# drv8353_based_bldc.net
KiCad netlist of a schematic drawn in EAGLE
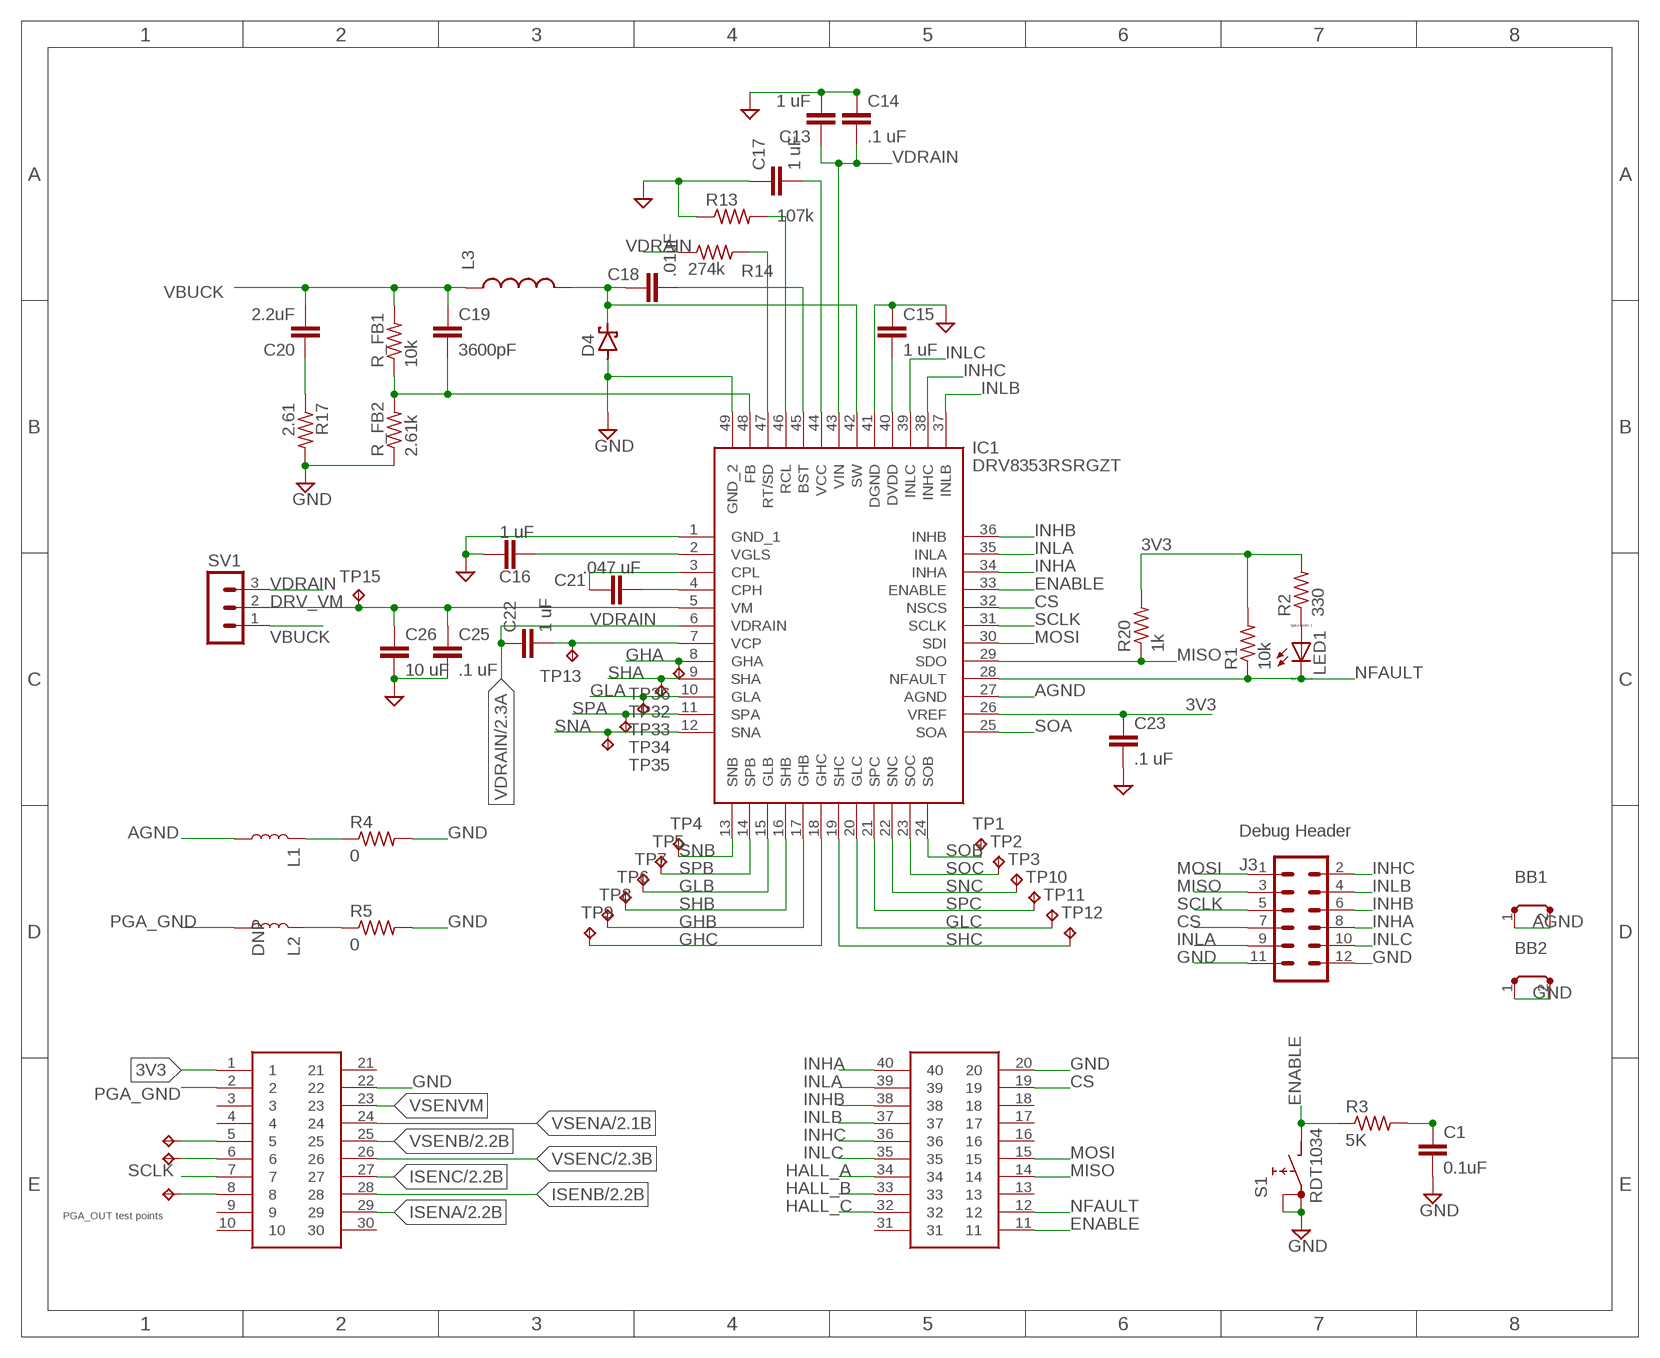
[diagram p0: schematic, sheet 1]
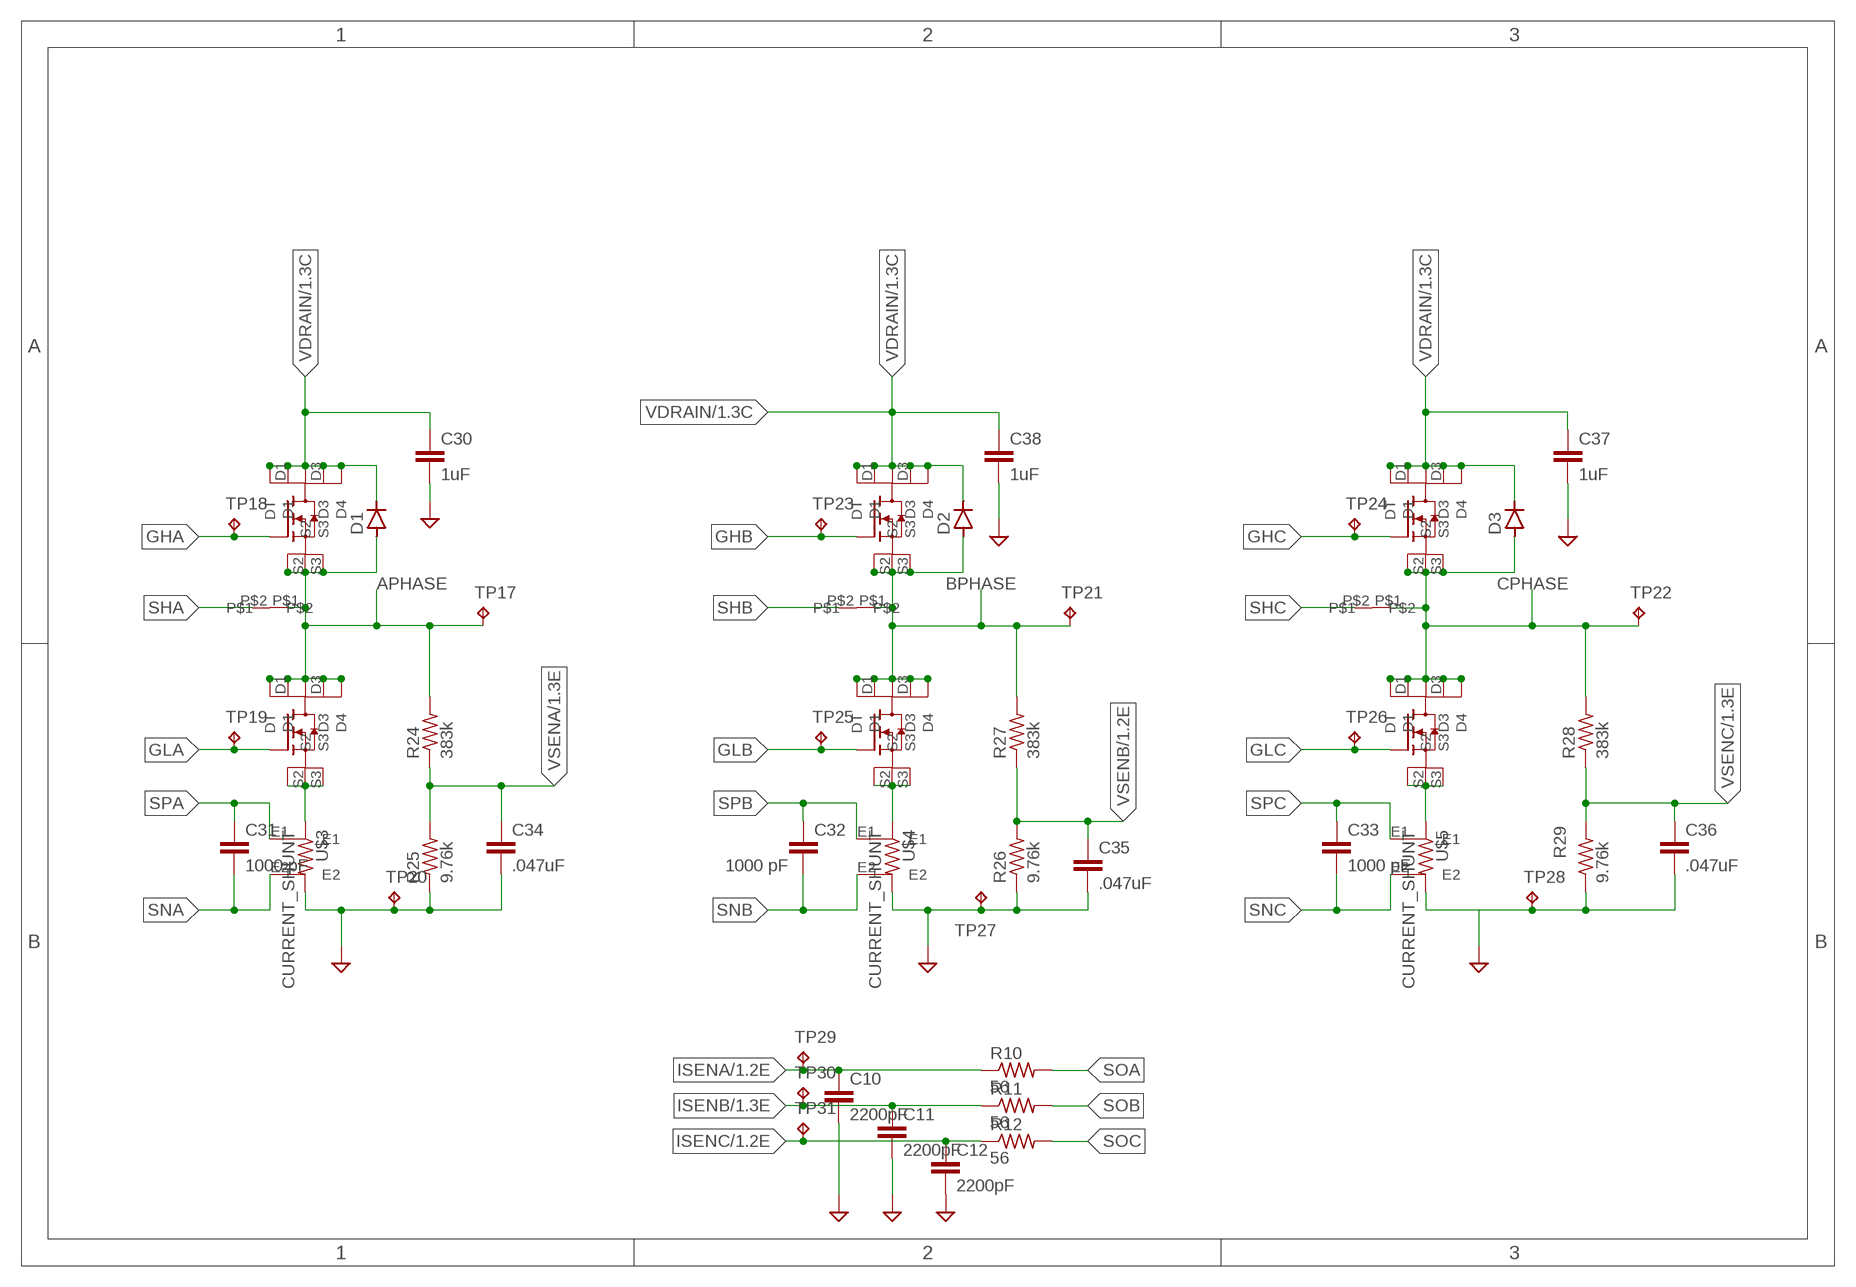
[diagram p1: schematic, sheet 2]
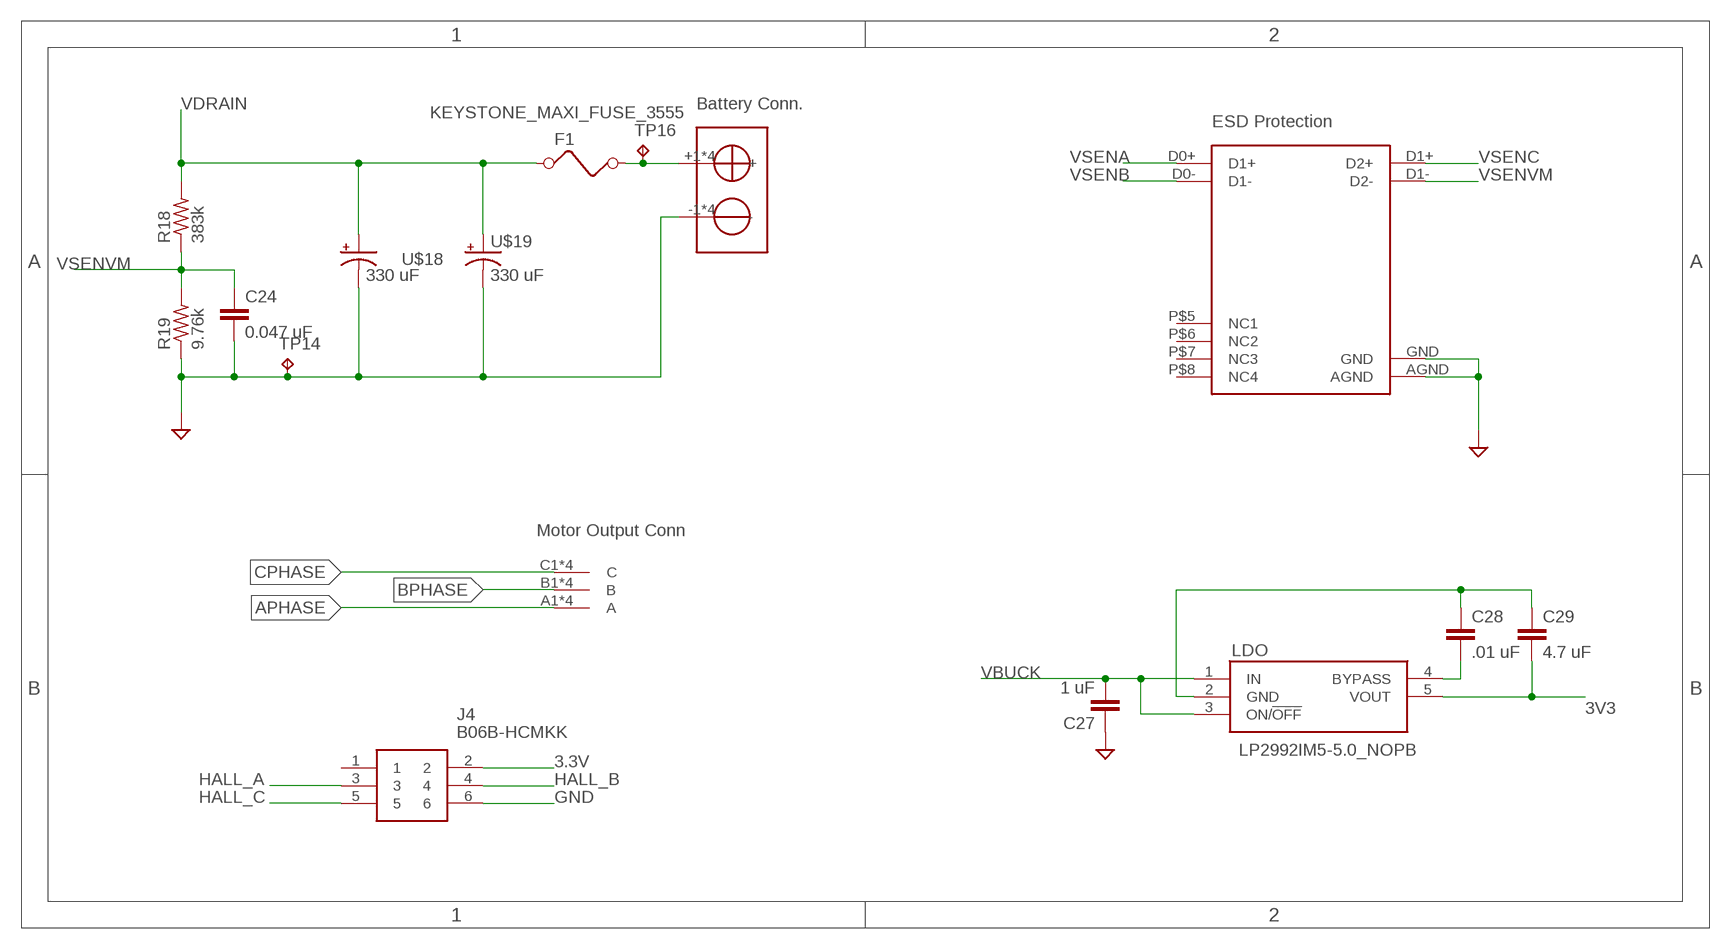
[diagram p2: schematic, sheet 3]

(export (version "E")
  (design (tool "Eeschema 10.0.6"))
  (components
    (comp (ref "BB1")
      (value "TE3/2")
      (footprint "eagle-import:TE3_2")
      (libsource (lib "eagle-import") (part "TE3/2"))
    )
    (comp (ref "BB2")
      (value "TE3/2")
      (footprint "eagle-import:TE3_2")
      (libsource (lib "eagle-import") (part "TE3/2"))
    )
    (comp (ref "C1")
      (value "0.1uF")
      (footprint "eagle-import:C0603K")
      (libsource (lib "eagle-import") (part "resistor_348_C-EUC0603K"))
    )
    (comp (ref "C13")
      (value "1 uF")
      (footprint "eagle-import:C1206K")
      (libsource (lib "eagle-import") (part "C-EUC1206K"))
    )
    (comp (ref "C14")
      (value ".1 uF")
      (footprint "eagle-import:C0805K")
      (libsource (lib "eagle-import") (part "resistor_348_C-EUC0805K"))
    )
    (comp (ref "C15")
      (value "1 uF")
      (footprint "eagle-import:C0603K")
      (libsource (lib "eagle-import") (part "C-EUC0603K"))
    )
    (comp (ref "C16")
      (value "1 uF")
      (footprint "eagle-import:C0603K")
      (libsource (lib "eagle-import") (part "C-EUC0603K"))
    )
    (comp (ref "C17")
      (value "1 uF")
      (footprint "eagle-import:C0603K")
      (libsource (lib "eagle-import") (part "C-EUC0603K"))
    )
    (comp (ref "C18")
      (value ".01uF")
      (footprint "eagle-import:C0603K")
      (libsource (lib "eagle-import") (part "C-EUC0603K"))
    )
    (comp (ref "C19")
      (value "3600pF")
      (footprint "eagle-import:C0603K")
      (libsource (lib "eagle-import") (part "C-EUC0603K"))
    )
    (comp (ref "C20")
      (value "2.2uF")
      (footprint "eagle-import:C0805K")
      (libsource (lib "eagle-import") (part "C-EUC0805K"))
    )
    (comp (ref "C21")
      (value ".047 uF")
      (footprint "eagle-import:C0805K")
      (libsource (lib "eagle-import") (part "C-EUC0805K"))
    )
    (comp (ref "C22")
      (value "1 uF")
      (footprint "eagle-import:C0603K")
      (libsource (lib "eagle-import") (part "resistor_348_C-EUC0603K"))
    )
    (comp (ref "C23")
      (value ".1 uF")
      (footprint "eagle-import:C0603K")
      (libsource (lib "eagle-import") (part "resistor_348_C-EUC0603K"))
    )
    (comp (ref "C25")
      (value ".1 uF")
      (footprint "eagle-import:C0805K")
      (libsource (lib "eagle-import") (part "C-EUC0805K"))
    )
    (comp (ref "C26")
      (value "10 uF")
      (footprint "eagle-import:C2220K")
      (libsource (lib "eagle-import") (part "C-EUC2220K"))
    )
    (comp (ref "D4")
      (value "DFLS1200")
      (footprint "eagle-import:DFLS1200")
      (fields (field (name "SPICEPREFIX") "B"))
      (libsource (lib "eagle-import") (part "DFLS1200"))
    )
    (comp (ref "IC1")
      (value "DRV8353RSRGZT")
      (footprint "eagle-import:QFN50P700X700X100-49N")
      (fields (field (name "MOUSER_PART_NUMBER") "595-DRV8353RSRGZT"))
      (libsource (lib "eagle-import") (part "DRV8353RSRGZT"))
    )
    (comp (ref "J3")
      (value "2X6 FEMALE")
      (footprint "eagle-import:2X6")
      (libsource (lib "eagle-import") (part "CONN_06X2PTH_FEMALE"))
    )
    (comp (ref "L1")
      (value "33nH/±5%/500mA")
      (footprint "eagle-import:0603")
      (libsource (lib "eagle-import") (part "INDUCTOR-0603-33NH"))
    )
    (comp (ref "L2")
      (value "DNP")
      (footprint "eagle-import:0603")
      (libsource (lib "eagle-import") (part "INDUCTOR-0603-33NH"))
    )
    (comp (ref "L3")
      (value "330 uH")
      (footprint "eagle-import:74404084331")
      (libsource (lib "eagle-import") (part "74404084331"))
    )
    (comp (ref "LED1")
      (value "LED_ESML0603")
      (footprint "eagle-import:LED_SML0603")
      (libsource (lib "eagle-import") (part "LED_ESML0603"))
    )
    (comp (ref "R1")
      (value "10k")
      (footprint "eagle-import:R0603")
      (libsource (lib "eagle-import") (part "R-US_R0603"))
    )
    (comp (ref "R2")
      (value "330")
      (footprint "eagle-import:R0603")
      (libsource (lib "eagle-import") (part "R-US_R0603"))
    )
    (comp (ref "R3")
      (value "5K")
      (footprint "eagle-import:R0603")
      (libsource (lib "eagle-import") (part "resistor_348_R-US_R0603"))
    )
    (comp (ref "R4")
      (value "0")
      (footprint "eagle-import:R0603")
      (libsource (lib "eagle-import") (part "resistor_348_R-US_R0603"))
    )
    (comp (ref "R5")
      (value "0")
      (footprint "eagle-import:R0603")
      (libsource (lib "eagle-import") (part "resistor_348_R-US_R0603"))
    )
    (comp (ref "R13")
      (value "107k")
      (footprint "eagle-import:R0603")
      (libsource (lib "eagle-import") (part "R-US_R0603"))
    )
    (comp (ref "R14")
      (value "274k")
      (footprint "eagle-import:R0603")
      (libsource (lib "eagle-import") (part "R-US_R0603"))
    )
    (comp (ref "R17")
      (value "2.61")
      (footprint "eagle-import:R0603")
      (libsource (lib "eagle-import") (part "R-US_R0603"))
    )
    (comp (ref "R20")
      (value "1k")
      (footprint "eagle-import:R0603")
      (libsource (lib "eagle-import") (part "R-US_R0603"))
    )
    (comp (ref "R_FB1")
      (value "10k")
      (footprint "eagle-import:R0603")
      (libsource (lib "eagle-import") (part "R-US_R0603"))
    )
    (comp (ref "R_FB2")
      (value "2.61k")
      (footprint "eagle-import:R0603")
      (libsource (lib "eagle-import") (part "R-US_R0603"))
    )
    (comp (ref "S1")
      (value "RDT1034")
      (footprint "eagle-import:RDT1034")
      (libsource (lib "eagle-import") (part "RDT1034"))
    )
    (comp (ref "SV1")
      (value "MA03-1")
      (footprint "eagle-import:MA03-1")
      (libsource (lib "eagle-import") (part "MA03-1"))
    )
    (comp (ref "TP1")
      (value "TPB1,27")
      (footprint "eagle-import:B1,27")
      (libsource (lib "eagle-import") (part "TPB1,27"))
    )
    (comp (ref "TP2")
      (value "TPB1,27")
      (footprint "eagle-import:B1,27")
      (libsource (lib "eagle-import") (part "TPB1,27"))
    )
    (comp (ref "TP3")
      (value "TPB1,27")
      (footprint "eagle-import:B1,27")
      (libsource (lib "eagle-import") (part "TPB1,27"))
    )
    (comp (ref "TP4")
      (value "TPB1,27")
      (footprint "eagle-import:B1,27")
      (libsource (lib "eagle-import") (part "TPB1,27"))
    )
    (comp (ref "TP5")
      (value "TPB1,27")
      (footprint "eagle-import:B1,27")
      (libsource (lib "eagle-import") (part "TPB1,27"))
    )
    (comp (ref "TP6")
      (value "TPB1,27")
      (footprint "eagle-import:B1,27")
      (libsource (lib "eagle-import") (part "TPB1,27"))
    )
    (comp (ref "TP7")
      (value "TPB1,27")
      (footprint "eagle-import:B1,27")
      (libsource (lib "eagle-import") (part "TPB1,27"))
    )
    (comp (ref "TP8")
      (value "TPB1,27")
      (footprint "eagle-import:B1,27")
      (libsource (lib "eagle-import") (part "TPB1,27"))
    )
    (comp (ref "TP9")
      (value "TPB1,27")
      (footprint "eagle-import:B1,27")
      (libsource (lib "eagle-import") (part "TPB1,27"))
    )
    (comp (ref "TP10")
      (value "TPB1,27")
      (footprint "eagle-import:B1,27")
      (libsource (lib "eagle-import") (part "TPB1,27"))
    )
    (comp (ref "TP11")
      (value "TPB1,27")
      (footprint "eagle-import:B1,27")
      (libsource (lib "eagle-import") (part "TPB1,27"))
    )
    (comp (ref "TP12")
      (value "TPB1,27")
      (footprint "eagle-import:B1,27")
      (libsource (lib "eagle-import") (part "TPB1,27"))
    )
    (comp (ref "TP13")
      (value "TPB1,27")
      (footprint "eagle-import:B1,27")
      (libsource (lib "eagle-import") (part "TPB1,27"))
    )
    (comp (ref "TP15")
      (value "TPB1,27")
      (footprint "eagle-import:B1,27")
      (libsource (lib "eagle-import") (part "TPB1,27"))
    )
    (comp (ref "TP32")
      (value "TPB1,27")
      (footprint "eagle-import:B1,27")
      (libsource (lib "eagle-import") (part "TPB1,27"))
    )
    (comp (ref "TP33")
      (value "TPB1,27")
      (footprint "eagle-import:B1,27")
      (libsource (lib "eagle-import") (part "TPB1,27"))
    )
    (comp (ref "TP34")
      (value "TPB1,27")
      (footprint "eagle-import:B1,27")
      (libsource (lib "eagle-import") (part "TPB1,27"))
    )
    (comp (ref "TP35")
      (value "TPB1,27")
      (footprint "eagle-import:B1,27")
      (libsource (lib "eagle-import") (part "TPB1,27"))
    )
    (comp (ref "TP36")
      (value "TPB1,27")
      (footprint "eagle-import:B1,27")
      (libsource (lib "eagle-import") (part "TPB1,27"))
    )
    (comp (ref "TP37")
      (value "TPB1,27")
      (footprint "eagle-import:B1,27")
      (libsource (lib "eagle-import") (part "TPB1,27"))
    )
    (comp (ref "TP38")
      (value "TPB1,27")
      (footprint "eagle-import:B1,27")
      (libsource (lib "eagle-import") (part "TPB1,27"))
    )
    (comp (ref "TP39")
      (value "TPB1,27")
      (footprint "eagle-import:B1,27")
      (libsource (lib "eagle-import") (part "TPB1,27"))
    )
    (comp (ref "U$2")
      (value "BOOSTER_DOCK")
      (footprint "eagle-import:BOOSTER_DOCK")
      (libsource (lib "eagle-import") (part "BOOSTER_DOCK"))
    )
    (comp (ref "C24")
      (value "0.047 uF")
      (footprint "eagle-import:C0603K")
      (libsource (lib "eagle-import") (part "C-EUC0603K"))
    )
    (comp (ref "C27")
      (value "1 uF")
      (footprint "eagle-import:C0805K")
      (libsource (lib "eagle-import") (part "C-EUC0805K"))
    )
    (comp (ref "C28")
      (value ".01 uF")
      (footprint "eagle-import:C0603K")
      (libsource (lib "eagle-import") (part "C-EUC0603K"))
    )
    (comp (ref "C29")
      (value "4.7 uF")
      (footprint "eagle-import:C1210K")
      (libsource (lib "eagle-import") (part "C-EUC1210K"))
    )
    (comp (ref "F1")
      (value "KEYSTONE_MAXI_FUSE_3555")
      (footprint "eagle-import:KEYSTONE_MAXI_FUSE_CLIP_3555")
      (libsource (lib "eagle-import") (part "KEYSTONE_MAXI_FUSE_3555"))
    )
    (comp (ref "J4")
      (value "B06B-HCMKK")
      (footprint "eagle-import:B06BHCMKK")
      (fields (field (name "MOUSER_PART_NUMBER") "306-B06B-HCMKK"))
      (libsource (lib "eagle-import") (part "B06B-HCMKK"))
    )
    (comp (ref "LDO")
      (value "LP2992IM5-5.0_NOPB")
      (footprint "eagle-import:SOT95P280X145-5N")
      (fields
        (field (name "MANUFACTURER_PART_NUMBER") "LP2992IM5-5.0/NOPB")
        (field (name "MOUSER_PART_NUMBER") "926-2992IM5-5.0/NOPB")
      )
      (libsource (lib "eagle-import") (part "LP2992IM5-5.0_NOPB"))
    )
    (comp (ref "R18")
      (value "383k")
      (footprint "eagle-import:R0603")
      (libsource (lib "eagle-import") (part "R-US_R0603"))
    )
    (comp (ref "R19")
      (value "9.76k")
      (footprint "eagle-import:R0603")
      (libsource (lib "eagle-import") (part "R-US_R0603"))
    )
    (comp (ref "TP14")
      (value "TPB1,27")
      (footprint "eagle-import:B1,27")
      (libsource (lib "eagle-import") (part "TPB1,27"))
    )
    (comp (ref "TP16")
      (value "TPB1,27")
      (footprint "eagle-import:B1,27")
      (libsource (lib "eagle-import") (part "TPB1,27"))
    )
    (comp (ref "TVS_DIODE")
      (value "TPD4S010DQAR")
      (footprint "eagle-import:TPD4S010DQAR")
      (libsource (lib "eagle-import") (part "TPD4S010DQAR"))
    )
    (comp (ref "U$1")
      (value "TRIPPLE-MINI-PP75")
      (footprint "eagle-import:TRIPPLE-MINI-PP75")
      (libsource (lib "eagle-import") (part "TRIPPLE-MINI-PP75"))
    )
    (comp (ref "U$16")
      (value "SB50")
      (footprint "eagle-import:MINI-SB-50")
      (libsource (lib "eagle-import") (part "SB50"))
    )
    (comp (ref "U$18")
      (value "330 uF")
      (footprint "eagle-import:SM_RADIAL_K16_1PRIMARY")
      (libsource (lib "eagle-import") (part "RADIALK16"))
    )
    (comp (ref "U$19")
      (value "330 uF")
      (footprint "eagle-import:SM_RADIAL_K16_1PRIMARY")
      (libsource (lib "eagle-import") (part "RADIALK16"))
    )
    (comp (ref "C10")
      (value "2200pF")
      (footprint "eagle-import:C0603K")
      (libsource (lib "eagle-import") (part "C-EUC0603K"))
    )
    (comp (ref "C11")
      (value "2200pF")
      (footprint "eagle-import:C0603K")
      (libsource (lib "eagle-import") (part "C-EUC0603K"))
    )
    (comp (ref "C12")
      (value "2200pF")
      (footprint "eagle-import:C0603K")
      (libsource (lib "eagle-import") (part "C-EUC0603K"))
    )
    (comp (ref "C30")
      (value "1uF")
      (footprint "eagle-import:C1206")
      (libsource (lib "eagle-import") (part "C-EUC1206"))
    )
    (comp (ref "C31")
      (value "1000 pF")
      (footprint "eagle-import:C0603K")
      (libsource (lib "eagle-import") (part "C-EUC0603K"))
    )
    (comp (ref "C32")
      (value "1000 pF")
      (footprint "eagle-import:C0603K")
      (libsource (lib "eagle-import") (part "C-EUC0603K"))
    )
    (comp (ref "C33")
      (value "1000 pF")
      (footprint "eagle-import:C0603K")
      (libsource (lib "eagle-import") (part "C-EUC0603K"))
    )
    (comp (ref "C34")
      (value ".047uF")
      (footprint "eagle-import:C0603K")
      (libsource (lib "eagle-import") (part "C-EUC0603K"))
    )
    (comp (ref "C35")
      (value ".047uF")
      (footprint "eagle-import:C0603K")
      (libsource (lib "eagle-import") (part "C-EUC0603K"))
    )
    (comp (ref "C36")
      (value ".047uF")
      (footprint "eagle-import:C0603K")
      (libsource (lib "eagle-import") (part "C-EUC0603K"))
    )
    (comp (ref "C37")
      (value "1uF")
      (footprint "eagle-import:C0603K")
      (libsource (lib "eagle-import") (part "C-EUC0603K"))
    )
    (comp (ref "C38")
      (value "1uF")
      (footprint "eagle-import:C0603K")
      (libsource (lib "eagle-import") (part "C-EUC0603K"))
    )
    (comp (ref "D1")
      (value "D-SOD123")
      (footprint "eagle-import:SOD123")
      (libsource (lib "eagle-import") (part "D-SOD123"))
    )
    (comp (ref "D2")
      (value "D-SOD123")
      (footprint "eagle-import:SOD123")
      (libsource (lib "eagle-import") (part "D-SOD123"))
    )
    (comp (ref "D3")
      (value "D-SOD123")
      (footprint "eagle-import:SOD123")
      (libsource (lib "eagle-import") (part "D-SOD123"))
    )
    (comp (ref "R10")
      (value "56")
      (footprint "eagle-import:R0603")
      (libsource (lib "eagle-import") (part "R-US_R0603"))
    )
    (comp (ref "R11")
      (value "56")
      (footprint "eagle-import:R0603")
      (libsource (lib "eagle-import") (part "R-US_R0603"))
    )
    (comp (ref "R12")
      (value "56")
      (footprint "eagle-import:R0603")
      (libsource (lib "eagle-import") (part "R-US_R0603"))
    )
    (comp (ref "R24")
      (value "383k")
      (footprint "eagle-import:R0603")
      (libsource (lib "eagle-import") (part "R-US_R0603"))
    )
    (comp (ref "R25")
      (value "9.76k")
      (footprint "eagle-import:R0603")
      (libsource (lib "eagle-import") (part "R-US_R0603"))
    )
    (comp (ref "R26")
      (value "9.76k")
      (footprint "eagle-import:R0603")
      (libsource (lib "eagle-import") (part "R-US_R0603"))
    )
    (comp (ref "R27")
      (value "383k")
      (footprint "eagle-import:R0603")
      (libsource (lib "eagle-import") (part "R-US_R0603"))
    )
    (comp (ref "R28")
      (value "383k")
      (footprint "eagle-import:R0603")
      (libsource (lib "eagle-import") (part "R-US_R0603"))
    )
    (comp (ref "R29")
      (value "9.76k")
      (footprint "eagle-import:R0603")
      (libsource (lib "eagle-import") (part "R-US_R0603"))
    )
    (comp (ref "TP17")
      (value "TPB1,27")
      (footprint "eagle-import:B1,27")
      (libsource (lib "eagle-import") (part "TPB1,27"))
    )
    (comp (ref "TP18")
      (value "TPB1,27")
      (footprint "eagle-import:B1,27")
      (libsource (lib "eagle-import") (part "TPB1,27"))
    )
    (comp (ref "TP19")
      (value "TPB1,27")
      (footprint "eagle-import:B1,27")
      (libsource (lib "eagle-import") (part "TPB1,27"))
    )
    (comp (ref "TP20")
      (value "TPB1,27")
      (footprint "eagle-import:B1,27")
      (libsource (lib "eagle-import") (part "TPB1,27"))
    )
    (comp (ref "TP21")
      (value "TPB1,27")
      (footprint "eagle-import:B1,27")
      (libsource (lib "eagle-import") (part "TPB1,27"))
    )
    (comp (ref "TP22")
      (value "TPB1,27")
      (footprint "eagle-import:B1,27")
      (libsource (lib "eagle-import") (part "TPB1,27"))
    )
    (comp (ref "TP23")
      (value "TPB1,27")
      (footprint "eagle-import:B1,27")
      (libsource (lib "eagle-import") (part "TPB1,27"))
    )
    (comp (ref "TP24")
      (value "TPB1,27")
      (footprint "eagle-import:B1,27")
      (libsource (lib "eagle-import") (part "TPB1,27"))
    )
    (comp (ref "TP25")
      (value "TPB1,27")
      (footprint "eagle-import:B1,27")
      (libsource (lib "eagle-import") (part "TPB1,27"))
    )
    (comp (ref "TP26")
      (value "TPB1,27")
      (footprint "eagle-import:B1,27")
      (libsource (lib "eagle-import") (part "TPB1,27"))
    )
    (comp (ref "TP27")
      (value "TPB1,27")
      (footprint "eagle-import:B1,27")
      (libsource (lib "eagle-import") (part "TPB1,27"))
    )
    (comp (ref "TP28")
      (value "TPB1,27")
      (footprint "eagle-import:B1,27")
      (libsource (lib "eagle-import") (part "TPB1,27"))
    )
    (comp (ref "TP29")
      (value "TPB1,27")
      (footprint "eagle-import:B1,27")
      (libsource (lib "eagle-import") (part "TPB1,27"))
    )
    (comp (ref "TP30")
      (value "TPB1,27")
      (footprint "eagle-import:B1,27")
      (libsource (lib "eagle-import") (part "TPB1,27"))
    )
    (comp (ref "TP31")
      (value "TPB1,27")
      (footprint "eagle-import:B1,27")
      (libsource (lib "eagle-import") (part "TPB1,27"))
    )
    (comp (ref "U$3")
      (value "CURRENT_SHUNT")
      (footprint "eagle-import:VISH_CSM3637_.002-2")
      (libsource (lib "eagle-import") (part "CURRENT_SHUNT"))
    )
    (comp (ref "U$4")
      (value "CURRENT_SHUNT")
      (footprint "eagle-import:VISH_CSM3637_.002-2")
      (libsource (lib "eagle-import") (part "CURRENT_SHUNT"))
    )
    (comp (ref "U$5")
      (value "CURRENT_SHUNT")
      (footprint "eagle-import:VISH_CSM3637_.002-2")
      (libsource (lib "eagle-import") (part "CURRENT_SHUNT"))
    )
    (comp (ref "U$14")
      (value "NVMTS1D2N08H")
      (footprint "eagle-import:PQFN88")
      (libsource (lib "eagle-import") (part "NVMTS1D2N08H"))
    )
    (comp (ref "U$20")
      (value "NVMTS1D2N08H")
      (footprint "eagle-import:PQFN88")
      (libsource (lib "eagle-import") (part "NVMTS1D2N08H"))
    )
    (comp (ref "U$21")
      (value "NVMTS1D2N08H")
      (footprint "eagle-import:PQFN88")
      (libsource (lib "eagle-import") (part "NVMTS1D2N08H"))
    )
    (comp (ref "U$22")
      (value "NVMTS1D2N08H")
      (footprint "eagle-import:PQFN88")
      (libsource (lib "eagle-import") (part "NVMTS1D2N08H"))
    )
    (comp (ref "U$23")
      (value "NVMTS1D2N08H")
      (footprint "eagle-import:PQFN88")
      (libsource (lib "eagle-import") (part "NVMTS1D2N08H"))
    )
    (comp (ref "U$24")
      (value "NVMTS1D2N08H")
      (footprint "eagle-import:PQFN88")
      (libsource (lib "eagle-import") (part "NVMTS1D2N08H"))
    )
    (comp (ref "U$25")
      (value "NET_TIE")
      (footprint "eagle-import:CNT")
      (libsource (lib "eagle-import") (part "NET_TIE"))
    )
    (comp (ref "U$27")
      (value "NET_TIE")
      (footprint "eagle-import:CNT")
      (libsource (lib "eagle-import") (part "NET_TIE"))
    )
    (comp (ref "U$30")
      (value "NET_TIE")
      (footprint "eagle-import:CNT")
      (libsource (lib "eagle-import") (part "NET_TIE"))
    )
  )
  (nets
    (net (code "1") (name "3.3V") (class "Default")
      (node (ref "J4") (pin "2") (pinfunction "2_2") (pintype "bidirectional"))
    )
    (net (code "2") (name "3V3") (class "Default")
      (node (ref "C23") (pin "1") (pinfunction "1_1") (pintype "passive"))
      (node (ref "C29") (pin "2") (pinfunction "2_2") (pintype "passive"))
      (node (ref "IC1") (pin "26") (pinfunction "VREF_26") (pintype "bidirectional"))
      (node (ref "LDO") (pin "5") (pinfunction "VOUT_5") (pintype "output"))
      (node (ref "R1") (pin "2") (pinfunction "2_2") (pintype "passive"))
      (node (ref "R2") (pin "2") (pinfunction "2_2") (pintype "passive"))
      (node (ref "R20") (pin "2") (pinfunction "2_2") (pintype "passive"))
      (node (ref "U$2") (pin "1") (pinfunction "1_1") (pintype "bidirectional"))
    )
    (net (code "3") (name "AGND") (class "Default")
      (node (ref "BB1") (pin "1") (pinfunction "P_1") (pintype "passive"))
      (node (ref "BB1") (pin "2") (pinfunction "P_2") (pintype "passive"))
      (node (ref "IC1") (pin "27") (pinfunction "AGND_27") (pintype "bidirectional"))
      (node (ref "L1") (pin "1") (pinfunction "1_1") (pintype "passive"))
    )
    (net (code "4") (name "APHASE") (class "Default")
      (node (ref "D1") (pin "2") (pinfunction "A_2") (pintype "passive"))
      (node (ref "R24") (pin "2") (pinfunction "2_2") (pintype "passive"))
      (node (ref "TP17") (pin "TP") (pinfunction "TP_TP") (pintype "input"))
      (node (ref "U$1") (pin "A1") (pinfunction "A_A1") (pintype "bidirectional"))
      (node (ref "U$1") (pin "A2") (pinfunction "A_A2") (pintype "bidirectional"))
      (node (ref "U$1") (pin "A3") (pinfunction "A_A3") (pintype "bidirectional"))
      (node (ref "U$1") (pin "A4") (pinfunction "A_A4") (pintype "bidirectional"))
      (node (ref "U$14") (pin "S1") (pinfunction "S1_S1") (pintype "passive"))
      (node (ref "U$14") (pin "S2") (pinfunction "S2_S2") (pintype "passive"))
      (node (ref "U$14") (pin "S3") (pinfunction "S3_S3") (pintype "passive"))
      (node (ref "U$20") (pin "D1") (pinfunction "D1_D1") (pintype "passive"))
      (node (ref "U$20") (pin "D2") (pinfunction "D2_D2") (pintype "passive"))
      (node (ref "U$20") (pin "D3") (pinfunction "D3_D3") (pintype "passive"))
      (node (ref "U$20") (pin "D4") (pinfunction "D4_D4") (pintype "passive"))
      (node (ref "U$20") (pin "DT") (pinfunction "DT_DT") (pintype "passive"))
      (node (ref "U$25") (pin "P$1") (pinfunction "P$1_P$1") (pintype "bidirectional"))
    )
    (net (code "5") (name "BPHASE") (class "Default")
      (node (ref "D2") (pin "2") (pinfunction "A_2") (pintype "passive"))
      (node (ref "R27") (pin "2") (pinfunction "2_2") (pintype "passive"))
      (node (ref "TP21") (pin "TP") (pinfunction "TP_TP") (pintype "input"))
      (node (ref "U$1") (pin "B1") (pinfunction "B_B1") (pintype "bidirectional"))
      (node (ref "U$1") (pin "B2") (pinfunction "B_B2") (pintype "bidirectional"))
      (node (ref "U$1") (pin "B3") (pinfunction "B_B3") (pintype "bidirectional"))
      (node (ref "U$1") (pin "B4") (pinfunction "B_B4") (pintype "bidirectional"))
      (node (ref "U$21") (pin "D1") (pinfunction "D1_D1") (pintype "passive"))
      (node (ref "U$21") (pin "D2") (pinfunction "D2_D2") (pintype "passive"))
      (node (ref "U$21") (pin "D3") (pinfunction "D3_D3") (pintype "passive"))
      (node (ref "U$21") (pin "D4") (pinfunction "D4_D4") (pintype "passive"))
      (node (ref "U$21") (pin "DT") (pinfunction "DT_DT") (pintype "passive"))
      (node (ref "U$22") (pin "S1") (pinfunction "S1_S1") (pintype "passive"))
      (node (ref "U$22") (pin "S2") (pinfunction "S2_S2") (pintype "passive"))
      (node (ref "U$22") (pin "S3") (pinfunction "S3_S3") (pintype "passive"))
      (node (ref "U$27") (pin "P$1") (pinfunction "P$1_P$1") (pintype "bidirectional"))
    )
    (net (code "6") (name "CPHASE") (class "Default")
      (node (ref "D3") (pin "2") (pinfunction "A_2") (pintype "passive"))
      (node (ref "R28") (pin "2") (pinfunction "2_2") (pintype "passive"))
      (node (ref "TP22") (pin "TP") (pinfunction "TP_TP") (pintype "input"))
      (node (ref "U$1") (pin "C1") (pinfunction "C_C1") (pintype "bidirectional"))
      (node (ref "U$1") (pin "C2") (pinfunction "C_C2") (pintype "bidirectional"))
      (node (ref "U$1") (pin "C3") (pinfunction "C_C3") (pintype "bidirectional"))
      (node (ref "U$1") (pin "C4") (pinfunction "C_C4") (pintype "bidirectional"))
      (node (ref "U$23") (pin "S1") (pinfunction "S1_S1") (pintype "passive"))
      (node (ref "U$23") (pin "S2") (pinfunction "S2_S2") (pintype "passive"))
      (node (ref "U$23") (pin "S3") (pinfunction "S3_S3") (pintype "passive"))
      (node (ref "U$24") (pin "D1") (pinfunction "D1_D1") (pintype "passive"))
      (node (ref "U$24") (pin "D2") (pinfunction "D2_D2") (pintype "passive"))
      (node (ref "U$24") (pin "D3") (pinfunction "D3_D3") (pintype "passive"))
      (node (ref "U$24") (pin "D4") (pinfunction "D4_D4") (pintype "passive"))
      (node (ref "U$24") (pin "DT") (pinfunction "DT_DT") (pintype "passive"))
      (node (ref "U$30") (pin "P$1") (pinfunction "P$1_P$1") (pintype "bidirectional"))
    )
    (net (code "7") (name "CS") (class "Default")
      (node (ref "IC1") (pin "32") (pinfunction "NSCS_32") (pintype "bidirectional"))
      (node (ref "J3") (pin "7") (pinfunction "7_7") (pintype "passive"))
      (node (ref "U$2") (pin "19") (pinfunction "19_19") (pintype "bidirectional"))
    )
    (net (code "8") (name "DRV_VM") (class "Default")
      (node (ref "C25") (pin "1") (pinfunction "1_1") (pintype "passive"))
      (node (ref "C26") (pin "1") (pinfunction "1_1") (pintype "passive"))
      (node (ref "IC1") (pin "5") (pinfunction "VM_5") (pintype "bidirectional"))
      (node (ref "SV1") (pin "2") (pinfunction "2_2") (pintype "passive"))
      (node (ref "TP15") (pin "TP") (pinfunction "TP_TP") (pintype "input"))
    )
    (net (code "9") (name "ENABLE") (class "Default")
      (node (ref "IC1") (pin "33") (pinfunction "ENABLE_33") (pintype "bidirectional"))
      (node (ref "R3") (pin "1") (pinfunction "1_1") (pintype "passive"))
      (node (ref "S1") (pin "B") (pinfunction "B_B") (pintype "passive"))
      (node (ref "U$2") (pin "11") (pinfunction "11_11") (pintype "bidirectional"))
    )
    (net (code "10") (name "GHA") (class "Default")
      (node (ref "IC1") (pin "8") (pinfunction "GHA_8") (pintype "bidirectional"))
      (node (ref "TP18") (pin "TP") (pinfunction "TP_TP") (pintype "input"))
      (node (ref "TP36") (pin "TP") (pinfunction "TP_TP") (pintype "input"))
      (node (ref "U$14") (pin "G") (pinfunction "G_G") (pintype "passive"))
    )
    (net (code "11") (name "GHB") (class "Default")
      (node (ref "IC1") (pin "17") (pinfunction "GHB_17") (pintype "bidirectional"))
      (node (ref "TP23") (pin "TP") (pinfunction "TP_TP") (pintype "input"))
      (node (ref "TP8") (pin "TP") (pinfunction "TP_TP") (pintype "input"))
      (node (ref "U$22") (pin "G") (pinfunction "G_G") (pintype "passive"))
    )
    (net (code "12") (name "GHC") (class "Default")
      (node (ref "IC1") (pin "18") (pinfunction "GHC_18") (pintype "bidirectional"))
      (node (ref "TP24") (pin "TP") (pinfunction "TP_TP") (pintype "input"))
      (node (ref "TP9") (pin "TP") (pinfunction "TP_TP") (pintype "input"))
      (node (ref "U$23") (pin "G") (pinfunction "G_G") (pintype "passive"))
    )
    (net (code "13") (name "GLA") (class "Default")
      (node (ref "IC1") (pin "10") (pinfunction "GLA_10") (pintype "bidirectional"))
      (node (ref "TP19") (pin "TP") (pinfunction "TP_TP") (pintype "input"))
      (node (ref "TP33") (pin "TP") (pinfunction "TP_TP") (pintype "input"))
      (node (ref "U$20") (pin "G") (pinfunction "G_G") (pintype "passive"))
    )
    (net (code "14") (name "GLB") (class "Default")
      (node (ref "IC1") (pin "15") (pinfunction "GLB_15") (pintype "bidirectional"))
      (node (ref "TP25") (pin "TP") (pinfunction "TP_TP") (pintype "input"))
      (node (ref "TP7") (pin "TP") (pinfunction "TP_TP") (pintype "input"))
      (node (ref "U$21") (pin "G") (pinfunction "G_G") (pintype "passive"))
    )
    (net (code "15") (name "GLC") (class "Default")
      (node (ref "IC1") (pin "20") (pinfunction "GLC_20") (pintype "bidirectional"))
      (node (ref "TP11") (pin "TP") (pinfunction "TP_TP") (pintype "input"))
      (node (ref "TP26") (pin "TP") (pinfunction "TP_TP") (pintype "input"))
      (node (ref "U$24") (pin "G") (pinfunction "G_G") (pintype "passive"))
    )
    (net (code "16") (name "GND") (class "Default")
      (node (ref "BB2") (pin "1") (pinfunction "P_1") (pintype "passive"))
      (node (ref "BB2") (pin "2") (pinfunction "P_2") (pintype "passive"))
      (node (ref "C1") (pin "2") (pinfunction "2_2") (pintype "passive"))
      (node (ref "C10") (pin "2") (pinfunction "2_2") (pintype "passive"))
      (node (ref "C11") (pin "2") (pinfunction "2_2") (pintype "passive"))
      (node (ref "C12") (pin "2") (pinfunction "2_2") (pintype "passive"))
      (node (ref "C13") (pin "2") (pinfunction "2_2") (pintype "passive"))
      (node (ref "C14") (pin "1") (pinfunction "1_1") (pintype "passive"))
      (node (ref "C15") (pin "1") (pinfunction "1_1") (pintype "passive"))
      (node (ref "C16") (pin "1") (pinfunction "1_1") (pintype "passive"))
      (node (ref "C17") (pin "1") (pinfunction "1_1") (pintype "passive"))
      (node (ref "C23") (pin "2") (pinfunction "2_2") (pintype "passive"))
      (node (ref "C24") (pin "2") (pinfunction "2_2") (pintype "passive"))
      (node (ref "C25") (pin "2") (pinfunction "2_2") (pintype "passive"))
      (node (ref "C26") (pin "2") (pinfunction "2_2") (pintype "passive"))
      (node (ref "C27") (pin "1") (pinfunction "1_1") (pintype "passive"))
      (node (ref "C30") (pin "2") (pinfunction "2_2") (pintype "passive"))
      (node (ref "C34") (pin "2") (pinfunction "2_2") (pintype "passive"))
      (node (ref "C35") (pin "2") (pinfunction "2_2") (pintype "passive"))
      (node (ref "C36") (pin "2") (pinfunction "2_2") (pintype "passive"))
      (node (ref "C37") (pin "2") (pinfunction "2_2") (pintype "passive"))
      (node (ref "C38") (pin "2") (pinfunction "2_2") (pintype "passive"))
      (node (ref "D4") (pin "GND") (pinfunction "GND_GND") (pintype "passive"))
      (node (ref "IC1") (pin "1") (pinfunction "GND_1_1") (pintype "bidirectional"))
      (node (ref "IC1") (pin "41") (pinfunction "DGND_41") (pintype "bidirectional"))
      (node (ref "IC1") (pin "49") (pinfunction "GND_2_49") (pintype "bidirectional"))
      (node (ref "J3") (pin "11") (pinfunction "11_11") (pintype "passive"))
      (node (ref "J3") (pin "12") (pinfunction "12_12") (pintype "passive"))
      (node (ref "J4") (pin "6") (pinfunction "6_6") (pintype "bidirectional"))
      (node (ref "R13") (pin "1") (pinfunction "1_1") (pintype "passive"))
      (node (ref "R17") (pin "2") (pinfunction "2_2") (pintype "passive"))
      (node (ref "R19") (pin "1") (pinfunction "1_1") (pintype "passive"))
      (node (ref "R25") (pin "1") (pinfunction "1_1") (pintype "passive"))
      (node (ref "R26") (pin "1") (pinfunction "1_1") (pintype "passive"))
      (node (ref "R29") (pin "1") (pinfunction "1_1") (pintype "passive"))
      (node (ref "R4") (pin "2") (pinfunction "2_2") (pintype "passive"))
      (node (ref "R5") (pin "2") (pinfunction "2_2") (pintype "passive"))
      (node (ref "R_FB2") (pin "1") (pinfunction "1_1") (pintype "passive"))
      (node (ref "S1") (pin "A") (pinfunction "A_A") (pintype "passive"))
      (node (ref "S1") (pin "A1") (pinfunction "A1_A1") (pintype "passive"))
      (node (ref "TP14") (pin "TP") (pinfunction "TP_TP") (pintype "input"))
      (node (ref "TP20") (pin "TP") (pinfunction "TP_TP") (pintype "input"))
      (node (ref "TP27") (pin "TP") (pinfunction "TP_TP") (pintype "input"))
      (node (ref "TP28") (pin "TP") (pinfunction "TP_TP") (pintype "input"))
      (node (ref "TVS_DIODE") (pin "AGND") (pinfunction "AGND_AGND") (pintype "bidirectional"))
      (node (ref "TVS_DIODE") (pin "GND") (pinfunction "GND_GND") (pintype "bidirectional"))
      (node (ref "U$16") (pin "-1") (pinfunction "-_-1") (pintype "bidirectional"))
      (node (ref "U$16") (pin "-2") (pinfunction "-_-2") (pintype "bidirectional"))
      (node (ref "U$16") (pin "-3") (pinfunction "-_-3") (pintype "bidirectional"))
      (node (ref "U$16") (pin "-4") (pinfunction "-_-4") (pintype "bidirectional"))
      (node (ref "U$18") (pin "-") (pinfunction "-_-") (pintype "passive"))
      (node (ref "U$19") (pin "-") (pinfunction "-_-") (pintype "passive"))
      (node (ref "U$2") (pin "20") (pinfunction "20_20") (pintype "bidirectional"))
      (node (ref "U$2") (pin "22") (pinfunction "22_22") (pintype "bidirectional"))
      (node (ref "U$3") (pin "I2") (pinfunction "I2_I2") (pintype "passive"))
      (node (ref "U$4") (pin "I2") (pinfunction "I2_I2") (pintype "passive"))
      (node (ref "U$5") (pin "I2") (pinfunction "I2_I2") (pintype "passive"))
    )
    (net (code "17") (name "HALL_A") (class "Default")
      (node (ref "J4") (pin "3") (pinfunction "3_3") (pintype "bidirectional"))
      (node (ref "U$2") (pin "34") (pinfunction "34_34") (pintype "bidirectional"))
    )
    (net (code "18") (name "HALL_B") (class "Default")
      (node (ref "J4") (pin "4") (pinfunction "4_4") (pintype "bidirectional"))
      (node (ref "U$2") (pin "33") (pinfunction "33_33") (pintype "bidirectional"))
    )
    (net (code "19") (name "HALL_C") (class "Default")
      (node (ref "J4") (pin "5") (pinfunction "5_5") (pintype "bidirectional"))
      (node (ref "U$2") (pin "32") (pinfunction "32_32") (pintype "bidirectional"))
    )
    (net (code "20") (name "INHA") (class "Default")
      (node (ref "IC1") (pin "34") (pinfunction "INHA_34") (pintype "bidirectional"))
      (node (ref "J3") (pin "8") (pinfunction "8_8") (pintype "passive"))
      (node (ref "U$2") (pin "40") (pinfunction "40_40") (pintype "bidirectional"))
    )
    (net (code "21") (name "INHB") (class "Default")
      (node (ref "IC1") (pin "36") (pinfunction "INHB_36") (pintype "bidirectional"))
      (node (ref "J3") (pin "6") (pinfunction "6_6") (pintype "passive"))
      (node (ref "U$2") (pin "38") (pinfunction "38_38") (pintype "bidirectional"))
    )
    (net (code "22") (name "INHC") (class "Default")
      (node (ref "IC1") (pin "38") (pinfunction "INHC_38") (pintype "bidirectional"))
      (node (ref "J3") (pin "2") (pinfunction "2_2") (pintype "passive"))
      (node (ref "U$2") (pin "36") (pinfunction "36_36") (pintype "bidirectional"))
    )
    (net (code "23") (name "INLA") (class "Default")
      (node (ref "IC1") (pin "35") (pinfunction "INLA_35") (pintype "bidirectional"))
      (node (ref "J3") (pin "9") (pinfunction "9_9") (pintype "passive"))
      (node (ref "U$2") (pin "39") (pinfunction "39_39") (pintype "bidirectional"))
    )
    (net (code "24") (name "INLB") (class "Default")
      (node (ref "IC1") (pin "37") (pinfunction "INLB_37") (pintype "bidirectional"))
      (node (ref "J3") (pin "4") (pinfunction "4_4") (pintype "passive"))
      (node (ref "U$2") (pin "37") (pinfunction "37_37") (pintype "bidirectional"))
    )
    (net (code "25") (name "INLC") (class "Default")
      (node (ref "IC1") (pin "39") (pinfunction "INLC_39") (pintype "bidirectional"))
      (node (ref "J3") (pin "10") (pinfunction "10_10") (pintype "passive"))
      (node (ref "U$2") (pin "35") (pinfunction "35_35") (pintype "bidirectional"))
    )
    (net (code "26") (name "ISENA") (class "Default")
      (node (ref "C10") (pin "1") (pinfunction "1_1") (pintype "passive"))
      (node (ref "R10") (pin "1") (pinfunction "1_1") (pintype "passive"))
      (node (ref "TP29") (pin "TP") (pinfunction "TP_TP") (pintype "input"))
      (node (ref "U$2") (pin "29") (pinfunction "29_29") (pintype "bidirectional"))
    )
    (net (code "27") (name "ISENB") (class "Default")
      (node (ref "C11") (pin "1") (pinfunction "1_1") (pintype "passive"))
      (node (ref "R11") (pin "1") (pinfunction "1_1") (pintype "passive"))
      (node (ref "TP30") (pin "TP") (pinfunction "TP_TP") (pintype "input"))
      (node (ref "U$2") (pin "28") (pinfunction "28_28") (pintype "bidirectional"))
    )
    (net (code "28") (name "ISENC") (class "Default")
      (node (ref "C12") (pin "1") (pinfunction "1_1") (pintype "passive"))
      (node (ref "R12") (pin "1") (pinfunction "1_1") (pintype "passive"))
      (node (ref "TP31") (pin "TP") (pinfunction "TP_TP") (pintype "input"))
      (node (ref "U$2") (pin "27") (pinfunction "27_27") (pintype "bidirectional"))
    )
    (net (code "29") (name "MISO") (class "Default")
      (node (ref "IC1") (pin "29") (pinfunction "SDO_29") (pintype "bidirectional"))
      (node (ref "J3") (pin "3") (pinfunction "3_3") (pintype "passive"))
      (node (ref "R20") (pin "1") (pinfunction "1_1") (pintype "passive"))
      (node (ref "U$2") (pin "14") (pinfunction "14_14") (pintype "bidirectional"))
    )
    (net (code "30") (name "MOSI") (class "Default")
      (node (ref "IC1") (pin "30") (pinfunction "SDI_30") (pintype "bidirectional"))
      (node (ref "J3") (pin "1") (pinfunction "1_1") (pintype "passive"))
      (node (ref "U$2") (pin "15") (pinfunction "15_15") (pintype "bidirectional"))
    )
    (net (code "31") (name "NFAULT") (class "Default")
      (node (ref "IC1") (pin "28") (pinfunction "NFAULT_28") (pintype "bidirectional"))
      (node (ref "LED1") (pin "C") (pinfunction "C_C") (pintype "passive"))
      (node (ref "R1") (pin "1") (pinfunction "1_1") (pintype "passive"))
      (node (ref "U$2") (pin "12") (pinfunction "12_12") (pintype "bidirectional"))
    )
    (net (code "32") (name "Net-(C1-Pad1)") (class "Default")
      (node (ref "C1") (pin "1") (pinfunction "1_1") (pintype "passive"))
      (node (ref "R3") (pin "2") (pinfunction "2_2") (pintype "passive"))
    )
    (net (code "33") (name "Net-(C20-Pad1)") (class "Default")
      (node (ref "C20") (pin "1") (pinfunction "1_1") (pintype "passive"))
      (node (ref "R17") (pin "1") (pinfunction "1_1") (pintype "passive"))
    )
    (net (code "34") (name "Net-(F1-2-PadB1)") (class "Default")
      (node (ref "F1") (pin "B1") (pinfunction "2_B1") (pintype "passive"))
      (node (ref "F1") (pin "B2") (pinfunction "2_B2") (pintype "passive"))
      (node (ref "TP16") (pin "TP") (pinfunction "TP_TP") (pintype "input"))
      (node (ref "U$16") (pin "+1") (pinfunction "+_+1") (pintype "bidirectional"))
      (node (ref "U$16") (pin "+2") (pinfunction "+_+2") (pintype "bidirectional"))
      (node (ref "U$16") (pin "+3") (pinfunction "+_+3") (pintype "bidirectional"))
      (node (ref "U$16") (pin "+4") (pinfunction "+_+4") (pintype "bidirectional"))
    )
    (net (code "35") (name "Net-(IC1-BST)") (class "Default")
      (node (ref "C18") (pin "2") (pinfunction "2_2") (pintype "passive"))
      (node (ref "IC1") (pin "45") (pinfunction "BST_45") (pintype "bidirectional"))
    )
    (net (code "36") (name "Net-(IC1-CPH)") (class "Default")
      (node (ref "C21") (pin "2") (pinfunction "2_2") (pintype "passive"))
      (node (ref "IC1") (pin "4") (pinfunction "CPH_4") (pintype "bidirectional"))
    )
    (net (code "37") (name "Net-(IC1-CPL)") (class "Default")
      (node (ref "C21") (pin "1") (pinfunction "1_1") (pintype "passive"))
      (node (ref "IC1") (pin "3") (pinfunction "CPL_3") (pintype "bidirectional"))
    )
    (net (code "38") (name "Net-(IC1-DVDD)") (class "Default")
      (node (ref "C15") (pin "2") (pinfunction "2_2") (pintype "passive"))
      (node (ref "IC1") (pin "40") (pinfunction "DVDD_40") (pintype "bidirectional"))
    )
    (net (code "39") (name "Net-(IC1-FB)") (class "Default")
      (node (ref "C19") (pin "2") (pinfunction "2_2") (pintype "passive"))
      (node (ref "IC1") (pin "48") (pinfunction "FB_48") (pintype "bidirectional"))
      (node (ref "R_FB1") (pin "1") (pinfunction "1_1") (pintype "passive"))
      (node (ref "R_FB2") (pin "2") (pinfunction "2_2") (pintype "passive"))
    )
    (net (code "40") (name "Net-(IC1-RCL)") (class "Default")
      (node (ref "IC1") (pin "46") (pinfunction "RCL_46") (pintype "bidirectional"))
      (node (ref "R13") (pin "2") (pinfunction "2_2") (pintype "passive"))
    )
    (net (code "41") (name "Net-(IC1-RT{slash}SD)") (class "Default")
      (node (ref "IC1") (pin "47") (pinfunction "RT/SD_47") (pintype "bidirectional"))
      (node (ref "R14") (pin "2") (pinfunction "2_2") (pintype "passive"))
    )
    (net (code "42") (name "Net-(IC1-SW)") (class "Default")
      (node (ref "C18") (pin "1") (pinfunction "1_1") (pintype "passive"))
      (node (ref "D4") (pin "LINE") (pinfunction "LINE_LINE") (pintype "passive"))
      (node (ref "IC1") (pin "42") (pinfunction "SW_42") (pintype "bidirectional"))
      (node (ref "L3") (pin "P$2") (pinfunction "2_P$2") (pintype "passive"))
    )
    (net (code "43") (name "Net-(IC1-VCC)") (class "Default")
      (node (ref "C17") (pin "2") (pinfunction "2_2") (pintype "passive"))
      (node (ref "IC1") (pin "44") (pinfunction "VCC_44") (pintype "bidirectional"))
    )
    (net (code "44") (name "Net-(IC1-VCP)") (class "Default")
      (node (ref "C22") (pin "2") (pinfunction "2_2") (pintype "passive"))
      (node (ref "IC1") (pin "7") (pinfunction "VCP_7") (pintype "bidirectional"))
      (node (ref "TP13") (pin "TP") (pinfunction "TP_TP") (pintype "input"))
    )
    (net (code "45") (name "Net-(IC1-VGLS)") (class "Default")
      (node (ref "C16") (pin "2") (pinfunction "2_2") (pintype "passive"))
      (node (ref "IC1") (pin "2") (pinfunction "VGLS_2") (pintype "bidirectional"))
    )
    (net (code "46") (name "Net-(L1-Pad2)") (class "Default")
      (node (ref "L1") (pin "2") (pinfunction "2_2") (pintype "passive"))
      (node (ref "R4") (pin "1") (pinfunction "1_1") (pintype "passive"))
    )
    (net (code "47") (name "Net-(L2-Pad2)") (class "Default")
      (node (ref "L2") (pin "2") (pinfunction "2_2") (pintype "passive"))
      (node (ref "R5") (pin "1") (pinfunction "1_1") (pintype "passive"))
    )
    (net (code "48") (name "Net-(LDO-BYPASS)") (class "Default")
      (node (ref "C28") (pin "2") (pinfunction "2_2") (pintype "passive"))
      (node (ref "LDO") (pin "4") (pinfunction "BYPASS_4") (pintype "bidirectional"))
    )
    (net (code "49") (name "Net-(LDO-GND)") (class "Default")
      (node (ref "C28") (pin "1") (pinfunction "1_1") (pintype "passive"))
      (node (ref "C29") (pin "1") (pinfunction "1_1") (pintype "passive"))
      (node (ref "LDO") (pin "2") (pinfunction "GND_2") (pintype "power_in"))
    )
    (net (code "50") (name "Net-(LED1-PadA)") (class "Default")
      (node (ref "LED1") (pin "A") (pinfunction "A_A") (pintype "passive"))
      (node (ref "R2") (pin "1") (pinfunction "1_1") (pintype "passive"))
    )
    (net (code "51") (name "Net-(TP37-PadTP)") (class "Default")
      (node (ref "TP37") (pin "TP") (pinfunction "TP_TP") (pintype "input"))
      (node (ref "U$2") (pin "5") (pinfunction "5_5") (pintype "bidirectional"))
    )
    (net (code "52") (name "Net-(TP38-PadTP)") (class "Default")
      (node (ref "TP38") (pin "TP") (pinfunction "TP_TP") (pintype "input"))
      (node (ref "U$2") (pin "6") (pinfunction "6_6") (pintype "bidirectional"))
    )
    (net (code "53") (name "Net-(TP39-PadTP)") (class "Default")
      (node (ref "TP39") (pin "TP") (pinfunction "TP_TP") (pintype "input"))
      (node (ref "U$2") (pin "8") (pinfunction "8_8") (pintype "bidirectional"))
    )
    (net (code "54") (name "Net-(U$20-PadS1)") (class "Default")
      (node (ref "U$20") (pin "S1") (pinfunction "S1_S1") (pintype "passive"))
      (node (ref "U$20") (pin "S2") (pinfunction "S2_S2") (pintype "passive"))
      (node (ref "U$20") (pin "S3") (pinfunction "S3_S3") (pintype "passive"))
      (node (ref "U$3") (pin "I1") (pinfunction "I1_I1") (pintype "passive"))
    )
    (net (code "55") (name "Net-(U$21-PadS1)") (class "Default")
      (node (ref "U$21") (pin "S1") (pinfunction "S1_S1") (pintype "passive"))
      (node (ref "U$21") (pin "S2") (pinfunction "S2_S2") (pintype "passive"))
      (node (ref "U$21") (pin "S3") (pinfunction "S3_S3") (pintype "passive"))
      (node (ref "U$4") (pin "I1") (pinfunction "I1_I1") (pintype "passive"))
    )
    (net (code "56") (name "Net-(U$24-PadS1)") (class "Default")
      (node (ref "U$24") (pin "S1") (pinfunction "S1_S1") (pintype "passive"))
      (node (ref "U$24") (pin "S2") (pinfunction "S2_S2") (pintype "passive"))
      (node (ref "U$24") (pin "S3") (pinfunction "S3_S3") (pintype "passive"))
      (node (ref "U$5") (pin "I1") (pinfunction "I1_I1") (pintype "passive"))
    )
    (net (code "57") (name "PGA_GND") (class "Default")
      (node (ref "L2") (pin "1") (pinfunction "1_1") (pintype "passive"))
      (node (ref "U$2") (pin "2") (pinfunction "2_2") (pintype "bidirectional"))
    )
    (net (code "58") (name "SCLK") (class "Default")
      (node (ref "IC1") (pin "31") (pinfunction "SCLK_31") (pintype "bidirectional"))
      (node (ref "J3") (pin "5") (pinfunction "5_5") (pintype "passive"))
      (node (ref "U$2") (pin "7") (pinfunction "7_7") (pintype "bidirectional"))
    )
    (net (code "59") (name "SHA") (class "Default")
      (node (ref "IC1") (pin "9") (pinfunction "SHA_9") (pintype "bidirectional"))
      (node (ref "TP32") (pin "TP") (pinfunction "TP_TP") (pintype "input"))
      (node (ref "U$25") (pin "P$2") (pinfunction "P$2_P$2") (pintype "bidirectional"))
    )
    (net (code "60") (name "SHB") (class "Default")
      (node (ref "IC1") (pin "16") (pinfunction "SHB_16") (pintype "bidirectional"))
      (node (ref "TP6") (pin "TP") (pinfunction "TP_TP") (pintype "input"))
      (node (ref "U$27") (pin "P$2") (pinfunction "P$2_P$2") (pintype "bidirectional"))
    )
    (net (code "61") (name "SHC") (class "Default")
      (node (ref "IC1") (pin "19") (pinfunction "SHC_19") (pintype "bidirectional"))
      (node (ref "TP12") (pin "TP") (pinfunction "TP_TP") (pintype "input"))
      (node (ref "U$30") (pin "P$2") (pinfunction "P$2_P$2") (pintype "bidirectional"))
    )
    (net (code "62") (name "SNA") (class "Default")
      (node (ref "C31") (pin "2") (pinfunction "2_2") (pintype "passive"))
      (node (ref "IC1") (pin "12") (pinfunction "SNA_12") (pintype "bidirectional"))
      (node (ref "TP35") (pin "TP") (pinfunction "TP_TP") (pintype "input"))
      (node (ref "U$3") (pin "E2") (pinfunction "E2_E2") (pintype "bidirectional"))
    )
    (net (code "63") (name "SNB") (class "Default")
      (node (ref "C32") (pin "2") (pinfunction "2_2") (pintype "passive"))
      (node (ref "IC1") (pin "13") (pinfunction "SNB_13") (pintype "bidirectional"))
      (node (ref "TP4") (pin "TP") (pinfunction "TP_TP") (pintype "input"))
      (node (ref "U$4") (pin "E2") (pinfunction "E2_E2") (pintype "bidirectional"))
    )
    (net (code "64") (name "SNC") (class "Default")
      (node (ref "C33") (pin "2") (pinfunction "2_2") (pintype "passive"))
      (node (ref "IC1") (pin "22") (pinfunction "SNC_22") (pintype "bidirectional"))
      (node (ref "TP3") (pin "TP") (pinfunction "TP_TP") (pintype "input"))
      (node (ref "U$5") (pin "E2") (pinfunction "E2_E2") (pintype "bidirectional"))
    )
    (net (code "65") (name "SOA") (class "Default")
      (node (ref "IC1") (pin "25") (pinfunction "SOA_25") (pintype "bidirectional"))
      (node (ref "R10") (pin "2") (pinfunction "2_2") (pintype "passive"))
    )
    (net (code "66") (name "SOB") (class "Default")
      (node (ref "IC1") (pin "24") (pinfunction "SOB_24") (pintype "bidirectional"))
      (node (ref "R11") (pin "2") (pinfunction "2_2") (pintype "passive"))
      (node (ref "TP1") (pin "TP") (pinfunction "TP_TP") (pintype "input"))
    )
    (net (code "67") (name "SOC") (class "Default")
      (node (ref "IC1") (pin "23") (pinfunction "SOC_23") (pintype "bidirectional"))
      (node (ref "R12") (pin "2") (pinfunction "2_2") (pintype "passive"))
      (node (ref "TP2") (pin "TP") (pinfunction "TP_TP") (pintype "input"))
    )
    (net (code "68") (name "SPA") (class "Default")
      (node (ref "C31") (pin "1") (pinfunction "1_1") (pintype "passive"))
      (node (ref "IC1") (pin "11") (pinfunction "SPA_11") (pintype "bidirectional"))
      (node (ref "TP34") (pin "TP") (pinfunction "TP_TP") (pintype "input"))
      (node (ref "U$3") (pin "E1") (pinfunction "E1_E1") (pintype "bidirectional"))
    )
    (net (code "69") (name "SPB") (class "Default")
      (node (ref "C32") (pin "1") (pinfunction "1_1") (pintype "passive"))
      (node (ref "IC1") (pin "14") (pinfunction "SPB_14") (pintype "bidirectional"))
      (node (ref "TP5") (pin "TP") (pinfunction "TP_TP") (pintype "input"))
      (node (ref "U$4") (pin "E1") (pinfunction "E1_E1") (pintype "bidirectional"))
    )
    (net (code "70") (name "SPC") (class "Default")
      (node (ref "C33") (pin "1") (pinfunction "1_1") (pintype "passive"))
      (node (ref "IC1") (pin "21") (pinfunction "SPC_21") (pintype "bidirectional"))
      (node (ref "TP10") (pin "TP") (pinfunction "TP_TP") (pintype "input"))
      (node (ref "U$5") (pin "E1") (pinfunction "E1_E1") (pintype "bidirectional"))
    )
    (net (code "71") (name "VBUCK") (class "Default")
      (node (ref "C19") (pin "1") (pinfunction "1_1") (pintype "passive"))
      (node (ref "C20") (pin "2") (pinfunction "2_2") (pintype "passive"))
      (node (ref "C27") (pin "2") (pinfunction "2_2") (pintype "passive"))
      (node (ref "L3") (pin "P$1") (pinfunction "1_P$1") (pintype "passive"))
      (node (ref "LDO") (pin "1") (pinfunction "IN_1") (pintype "input"))
      (node (ref "LDO") (pin "3") (pinfunction "ON/~{OFF}_3") (pintype "bidirectional"))
      (node (ref "R_FB1") (pin "2") (pinfunction "2_2") (pintype "passive"))
      (node (ref "SV1") (pin "1") (pinfunction "1_1") (pintype "passive"))
    )
    (net (code "72") (name "VDRAIN") (class "Default")
      (node (ref "C13") (pin "1") (pinfunction "1_1") (pintype "passive"))
      (node (ref "C14") (pin "2") (pinfunction "2_2") (pintype "passive"))
      (node (ref "C22") (pin "1") (pinfunction "1_1") (pintype "passive"))
      (node (ref "C30") (pin "1") (pinfunction "1_1") (pintype "passive"))
      (node (ref "C37") (pin "1") (pinfunction "1_1") (pintype "passive"))
      (node (ref "C38") (pin "1") (pinfunction "1_1") (pintype "passive"))
      (node (ref "D1") (pin "1") (pinfunction "C_1") (pintype "passive"))
      (node (ref "D2") (pin "1") (pinfunction "C_1") (pintype "passive"))
      (node (ref "D3") (pin "1") (pinfunction "C_1") (pintype "passive"))
      (node (ref "F1") (pin "A1") (pinfunction "1_A1") (pintype "passive"))
      (node (ref "F1") (pin "A2") (pinfunction "1_A2") (pintype "passive"))
      (node (ref "IC1") (pin "43") (pinfunction "VIN_43") (pintype "bidirectional"))
      (node (ref "IC1") (pin "6") (pinfunction "VDRAIN_6") (pintype "bidirectional"))
      (node (ref "R14") (pin "1") (pinfunction "1_1") (pintype "passive"))
      (node (ref "R18") (pin "2") (pinfunction "2_2") (pintype "passive"))
      (node (ref "SV1") (pin "3") (pinfunction "3_3") (pintype "passive"))
      (node (ref "U$14") (pin "D1") (pinfunction "D1_D1") (pintype "passive"))
      (node (ref "U$14") (pin "D2") (pinfunction "D2_D2") (pintype "passive"))
      (node (ref "U$14") (pin "D3") (pinfunction "D3_D3") (pintype "passive"))
      (node (ref "U$14") (pin "D4") (pinfunction "D4_D4") (pintype "passive"))
      (node (ref "U$14") (pin "DT") (pinfunction "DT_DT") (pintype "passive"))
      (node (ref "U$18") (pin "+") (pinfunction "+_+") (pintype "passive"))
      (node (ref "U$19") (pin "+") (pinfunction "+_+") (pintype "passive"))
      (node (ref "U$22") (pin "D1") (pinfunction "D1_D1") (pintype "passive"))
      (node (ref "U$22") (pin "D2") (pinfunction "D2_D2") (pintype "passive"))
      (node (ref "U$22") (pin "D3") (pinfunction "D3_D3") (pintype "passive"))
      (node (ref "U$22") (pin "D4") (pinfunction "D4_D4") (pintype "passive"))
      (node (ref "U$22") (pin "DT") (pinfunction "DT_DT") (pintype "passive"))
      (node (ref "U$23") (pin "D1") (pinfunction "D1_D1") (pintype "passive"))
      (node (ref "U$23") (pin "D2") (pinfunction "D2_D2") (pintype "passive"))
      (node (ref "U$23") (pin "D3") (pinfunction "D3_D3") (pintype "passive"))
      (node (ref "U$23") (pin "D4") (pinfunction "D4_D4") (pintype "passive"))
      (node (ref "U$23") (pin "DT") (pinfunction "DT_DT") (pintype "passive"))
    )
    (net (code "73") (name "VSENA") (class "Default")
      (node (ref "C34") (pin "1") (pinfunction "1_1") (pintype "passive"))
      (node (ref "R24") (pin "1") (pinfunction "1_1") (pintype "passive"))
      (node (ref "R25") (pin "2") (pinfunction "2_2") (pintype "passive"))
      (node (ref "TVS_DIODE") (pin "D0+") (pinfunction "D1+_D0+") (pintype "bidirectional"))
      (node (ref "U$2") (pin "24") (pinfunction "24_24") (pintype "bidirectional"))
    )
    (net (code "74") (name "VSENB") (class "Default")
      (node (ref "C35") (pin "1") (pinfunction "1_1") (pintype "passive"))
      (node (ref "R26") (pin "2") (pinfunction "2_2") (pintype "passive"))
      (node (ref "R27") (pin "1") (pinfunction "1_1") (pintype "passive"))
      (node (ref "TVS_DIODE") (pin "D0-") (pinfunction "D1-_D0-") (pintype "bidirectional"))
      (node (ref "U$2") (pin "25") (pinfunction "25_25") (pintype "bidirectional"))
    )
    (net (code "75") (name "VSENC") (class "Default")
      (node (ref "C36") (pin "1") (pinfunction "1_1") (pintype "passive"))
      (node (ref "R28") (pin "1") (pinfunction "1_1") (pintype "passive"))
      (node (ref "R29") (pin "2") (pinfunction "2_2") (pintype "passive"))
      (node (ref "TVS_DIODE") (pin "D1+") (pinfunction "D2+_D1+") (pintype "bidirectional"))
      (node (ref "U$2") (pin "26") (pinfunction "26_26") (pintype "bidirectional"))
    )
    (net (code "76") (name "VSENVM") (class "Default")
      (node (ref "C24") (pin "1") (pinfunction "1_1") (pintype "passive"))
      (node (ref "R18") (pin "1") (pinfunction "1_1") (pintype "passive"))
      (node (ref "R19") (pin "2") (pinfunction "2_2") (pintype "passive"))
      (node (ref "TVS_DIODE") (pin "D1-") (pinfunction "D2-_D1-") (pintype "bidirectional"))
      (node (ref "U$2") (pin "23") (pinfunction "23_23") (pintype "bidirectional"))
    )
    (net (code "77") (name "unconnected-(J4-Pad1)") (class "Default")
      (node (ref "J4") (pin "1") (pinfunction "1_1") (pintype "bidirectional"))
    )
    (net (code "78") (name "unconnected-(TVS_DIODE-NC1-PadP$5)") (class "Default")
      (node (ref "TVS_DIODE") (pin "P$5") (pinfunction "NC1_P$5") (pintype "bidirectional"))
    )
    (net (code "79") (name "unconnected-(TVS_DIODE-NC2-PadP$6)") (class "Default")
      (node (ref "TVS_DIODE") (pin "P$6") (pinfunction "NC2_P$6") (pintype "bidirectional"))
    )
    (net (code "80") (name "unconnected-(TVS_DIODE-NC3-PadP$7)") (class "Default")
      (node (ref "TVS_DIODE") (pin "P$7") (pinfunction "NC3_P$7") (pintype "bidirectional"))
    )
    (net (code "81") (name "unconnected-(TVS_DIODE-NC4-PadP$8)") (class "Default")
      (node (ref "TVS_DIODE") (pin "P$8") (pinfunction "NC4_P$8") (pintype "bidirectional"))
    )
    (net (code "82") (name "unconnected-(U$2-Pad3)") (class "Default")
      (node (ref "U$2") (pin "3") (pinfunction "3_3") (pintype "bidirectional"))
    )
    (net (code "83") (name "unconnected-(U$2-Pad4)") (class "Default")
      (node (ref "U$2") (pin "4") (pinfunction "4_4") (pintype "bidirectional"))
    )
    (net (code "84") (name "unconnected-(U$2-Pad9)") (class "Default")
      (node (ref "U$2") (pin "9") (pinfunction "9_9") (pintype "bidirectional"))
    )
    (net (code "85") (name "unconnected-(U$2-Pad10)") (class "Default")
      (node (ref "U$2") (pin "10") (pinfunction "10_10") (pintype "bidirectional"))
    )
    (net (code "86") (name "unconnected-(U$2-Pad13)") (class "Default")
      (node (ref "U$2") (pin "13") (pinfunction "13_13") (pintype "bidirectional"))
    )
    (net (code "87") (name "unconnected-(U$2-Pad16)") (class "Default")
      (node (ref "U$2") (pin "16") (pinfunction "16_16") (pintype "bidirectional"))
    )
    (net (code "88") (name "unconnected-(U$2-Pad17)") (class "Default")
      (node (ref "U$2") (pin "17") (pinfunction "17_17") (pintype "bidirectional"))
    )
    (net (code "89") (name "unconnected-(U$2-Pad18)") (class "Default")
      (node (ref "U$2") (pin "18") (pinfunction "18_18") (pintype "bidirectional"))
    )
    (net (code "90") (name "unconnected-(U$2-Pad21)") (class "Default")
      (node (ref "U$2") (pin "21") (pinfunction "21_21") (pintype "bidirectional"))
    )
    (net (code "91") (name "unconnected-(U$2-Pad30)") (class "Default")
      (node (ref "U$2") (pin "30") (pinfunction "30_30") (pintype "bidirectional"))
    )
    (net (code "92") (name "unconnected-(U$2-Pad31)") (class "Default")
      (node (ref "U$2") (pin "31") (pinfunction "31_31") (pintype "bidirectional"))
    )
  )
)
